# key.net
KiCad netlist of a schematic drawn in Altium Designer
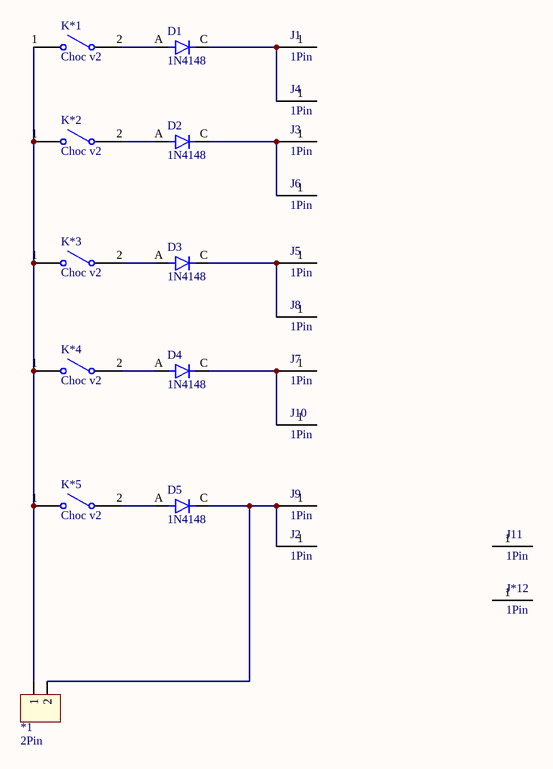
[diagram p0: key.SchDoc]

(export (version "E")
  (design (tool "Eeschema 10.0.6"))
  (components
    (comp (ref "*1")
      (value "2Pin")
      (footprint "TH2.54-2pin")
      (libsource (lib "MyOwnSchlib_ver1.2") (part "2Pin"))
    )
    (comp (ref "D1")
      (value "1N4148")
      (footprint "1N4148")
      (libsource (lib "MyOwnSchlib_ver1.2") (part "1N4148"))
    )
    (comp (ref "D2")
      (value "1N4148")
      (footprint "1N4148")
      (libsource (lib "MyOwnSchlib_ver1.2") (part "1N4148"))
    )
    (comp (ref "D3")
      (value "1N4148")
      (footprint "1N4148")
      (libsource (lib "MyOwnSchlib_ver1.2") (part "1N4148"))
    )
    (comp (ref "D4")
      (value "1N4148")
      (footprint "1N4148")
      (libsource (lib "MyOwnSchlib_ver1.2") (part "1N4148"))
    )
    (comp (ref "D5")
      (value "1N4148")
      (footprint "1N4148")
      (libsource (lib "MyOwnSchlib_ver1.2") (part "1N4148"))
    )
    (comp (ref "J*12") (value "1Pin") (footprint "1Pin") (libsource (lib "MyOwnSchlib_ver1.2") (part "1Pin")))
    (comp (ref "J1") (value "1Pin") (footprint "1Pin") (libsource (lib "MyOwnSchlib_ver1.2") (part "1Pin")))
    (comp (ref "J2") (value "1Pin") (footprint "1Pin") (libsource (lib "MyOwnSchlib_ver1.2") (part "1Pin")))
    (comp (ref "J3") (value "1Pin") (footprint "1Pin") (libsource (lib "MyOwnSchlib_ver1.2") (part "1Pin")))
    (comp (ref "J4") (value "1Pin") (footprint "1Pin") (libsource (lib "MyOwnSchlib_ver1.2") (part "1Pin")))
    (comp (ref "J5") (value "1Pin") (footprint "1Pin") (libsource (lib "MyOwnSchlib_ver1.2") (part "1Pin")))
    (comp (ref "J6") (value "1Pin") (footprint "1Pin") (libsource (lib "MyOwnSchlib_ver1.2") (part "1Pin")))
    (comp (ref "J7") (value "1Pin") (footprint "1Pin") (libsource (lib "MyOwnSchlib_ver1.2") (part "1Pin")))
    (comp (ref "J8") (value "1Pin") (footprint "1Pin") (libsource (lib "MyOwnSchlib_ver1.2") (part "1Pin")))
    (comp (ref "J9") (value "1Pin") (footprint "1Pin") (libsource (lib "MyOwnSchlib_ver1.2") (part "1Pin")))
    (comp (ref "J10") (value "1Pin") (footprint "1Pin") (libsource (lib "MyOwnSchlib_ver1.2") (part "1Pin")))
    (comp (ref "J11") (value "1Pin") (footprint "1Pin") (libsource (lib "MyOwnSchlib_ver1.2") (part "1Pin")))
    (comp (ref "K*1")
      (value "Choc v2")
      (footprint "Choco v2")
      (libsource (lib "MyOwnSchlib_ver1.2") (part "Choc v2"))
    )
    (comp (ref "K*2")
      (value "Choc v2")
      (footprint "Choco v2")
      (libsource (lib "MyOwnSchlib_ver1.2") (part "Choc v2"))
    )
    (comp (ref "K*3")
      (value "Choc v2")
      (footprint "Choco v2")
      (libsource (lib "MyOwnSchlib_ver1.2") (part "Choc v2"))
    )
    (comp (ref "K*4")
      (value "Choc v2")
      (footprint "Choco v2")
      (libsource (lib "MyOwnSchlib_ver1.2") (part "Choc v2"))
    )
    (comp (ref "K*5")
      (value "Choc v2")
      (footprint "Choco v2")
      (libsource (lib "MyOwnSchlib_ver1.2") (part "Choc v2"))
    )
  )
  (nets
    (net (code "1") (name "Net-(*1-Pad1)") (class "Default")
      (node (ref "*1") (pin "1") (pinfunction "1_1") (pintype "passive"))
      (node (ref "K*1") (pin "1") (pinfunction "1_1") (pintype "passive"))
      (node (ref "K*2") (pin "1") (pinfunction "1_1") (pintype "passive"))
      (node (ref "K*3") (pin "1") (pinfunction "1_1") (pintype "passive"))
      (node (ref "K*4") (pin "1") (pinfunction "1_1") (pintype "passive"))
      (node (ref "K*5") (pin "1") (pinfunction "1_1") (pintype "passive"))
    )
    (net (code "2") (name "Net-(D1-PadA)") (class "Default")
      (node (ref "D1") (pin "A") (pinfunction "A_A") (pintype "passive"))
      (node (ref "K*1") (pin "2") (pinfunction "2_2") (pintype "passive"))
    )
    (net (code "3") (name "Net-(D2-PadA)") (class "Default")
      (node (ref "D2") (pin "A") (pinfunction "A_A") (pintype "passive"))
      (node (ref "K*2") (pin "2") (pinfunction "2_2") (pintype "passive"))
    )
    (net (code "4") (name "Net-(D3-PadA)") (class "Default")
      (node (ref "D3") (pin "A") (pinfunction "A_A") (pintype "passive"))
      (node (ref "K*3") (pin "2") (pinfunction "2_2") (pintype "passive"))
    )
    (net (code "5") (name "Net-(D4-PadA)") (class "Default")
      (node (ref "D4") (pin "A") (pinfunction "A_A") (pintype "passive"))
      (node (ref "K*4") (pin "2") (pinfunction "2_2") (pintype "passive"))
    )
    (net (code "6") (name "Net-(D5-PadA)") (class "Default")
      (node (ref "D5") (pin "A") (pinfunction "A_A") (pintype "passive"))
      (node (ref "K*5") (pin "2") (pinfunction "2_2") (pintype "passive"))
    )
    (net (code "7") (name "Net-(J1-0)") (class "Default")
      (node (ref "D1") (pin "C") (pinfunction "C_C") (pintype "passive"))
      (node (ref "J1") (pin "1") (pinfunction "0_1") (pintype "passive"))
      (node (ref "J4") (pin "1") (pinfunction "0_1") (pintype "passive"))
    )
    (net (code "8") (name "Net-(J2-0)") (class "Default")
      (node (ref "*1") (pin "2") (pinfunction "2_2") (pintype "passive"))
      (node (ref "D5") (pin "C") (pinfunction "C_C") (pintype "passive"))
      (node (ref "J2") (pin "1") (pinfunction "0_1") (pintype "passive"))
      (node (ref "J9") (pin "1") (pinfunction "0_1") (pintype "passive"))
    )
    (net (code "9") (name "Net-(J3-0)") (class "Default")
      (node (ref "D2") (pin "C") (pinfunction "C_C") (pintype "passive"))
      (node (ref "J3") (pin "1") (pinfunction "0_1") (pintype "passive"))
      (node (ref "J6") (pin "1") (pinfunction "0_1") (pintype "passive"))
    )
    (net (code "10") (name "Net-(J5-0)") (class "Default")
      (node (ref "D3") (pin "C") (pinfunction "C_C") (pintype "passive"))
      (node (ref "J5") (pin "1") (pinfunction "0_1") (pintype "passive"))
      (node (ref "J8") (pin "1") (pinfunction "0_1") (pintype "passive"))
    )
    (net (code "11") (name "Net-(J10-0)") (class "Default")
      (node (ref "D4") (pin "C") (pinfunction "C_C") (pintype "passive"))
      (node (ref "J10") (pin "1") (pinfunction "0_1") (pintype "passive"))
      (node (ref "J7") (pin "1") (pinfunction "0_1") (pintype "passive"))
    )
    (net (code "12") (name "unconnected-(J*12-0-Pad1)") (class "Default")
      (node (ref "J*12") (pin "1") (pinfunction "0_1") (pintype "passive"))
    )
    (net (code "13") (name "unconnected-(J11-0-Pad1)") (class "Default")
      (node (ref "J11") (pin "1") (pinfunction "0_1") (pintype "passive"))
    )
  )
)
